# JetsonTK1_GPIO.net
KiCad netlist of a schematic drawn in EAGLE
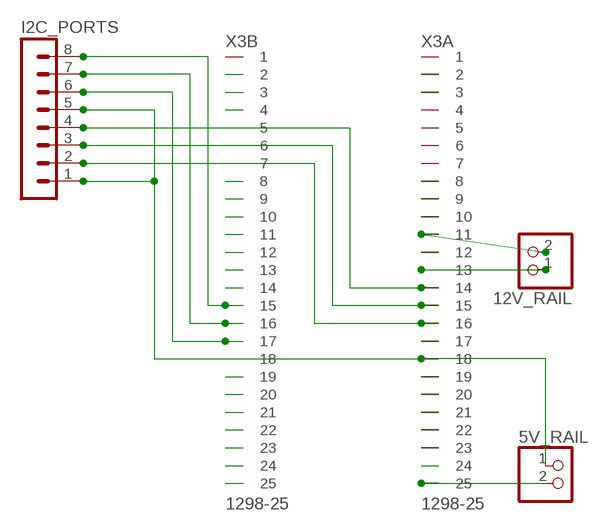
[diagram p0: schematic, sheet 1]

(export (version "E")
  (design (tool "Eeschema 10.0.6"))
  (components
    (comp (ref "5V_RAIL")
      (value "PINHD-1X2")
      (footprint "eagle-import:1X02")
      (libsource (lib "eagle-import") (part "PINHD-1X2"))
    )
    (comp (ref "12V_RAIL")
      (value "PINHD-1X2")
      (footprint "eagle-import:1X02")
      (libsource (lib "eagle-import") (part "PINHD-1X2"))
    )
    (comp (ref "I2C_PORTS")
      (value "MA08-1")
      (footprint "eagle-import:MA08-1")
      (libsource (lib "eagle-import") (part "MA08-1"))
    )
    (comp (ref "X3")
      (value "1298-25")
      (footprint "eagle-import:1298-25")
      (libsource (lib "eagle-import") (part "1298-25"))
    )
  )
  (nets
    (net (code "1") (name "Net-(X3A-11)") (class "Default")
      (node (ref "12V_RAIL") (pin "2") (pinfunction "2_2") (pintype "passive"))
      (node (ref "X3") (pin "A11") (pinfunction "11_A11") (pintype "passive"))
    )
    (net (code "2") (name "Net-(X3A-13)") (class "Default")
      (node (ref "12V_RAIL") (pin "1") (pinfunction "1_1") (pintype "passive"))
      (node (ref "X3") (pin "A13") (pinfunction "13_A13") (pintype "passive"))
    )
    (net (code "3") (name "Net-(X3A-14)") (class "Default")
      (node (ref "I2C_PORTS") (pin "4") (pinfunction "4_4") (pintype "passive"))
      (node (ref "X3") (pin "A14") (pinfunction "14_A14") (pintype "passive"))
    )
    (net (code "4") (name "Net-(X3A-15)") (class "Default")
      (node (ref "I2C_PORTS") (pin "3") (pinfunction "3_3") (pintype "passive"))
      (node (ref "X3") (pin "A15") (pinfunction "15_A15") (pintype "passive"))
    )
    (net (code "5") (name "Net-(X3A-16)") (class "Default")
      (node (ref "I2C_PORTS") (pin "2") (pinfunction "2_2") (pintype "passive"))
      (node (ref "X3") (pin "A16") (pinfunction "16_A16") (pintype "passive"))
    )
    (net (code "6") (name "Net-(X3A-18)") (class "Default")
      (node (ref "5V_RAIL") (pin "1") (pinfunction "1_1") (pintype "passive"))
      (node (ref "I2C_PORTS") (pin "1") (pinfunction "1_1") (pintype "passive"))
      (node (ref "I2C_PORTS") (pin "5") (pinfunction "5_5") (pintype "passive"))
      (node (ref "X3") (pin "A18") (pinfunction "18_A18") (pintype "passive"))
    )
    (net (code "7") (name "Net-(X3A-25)") (class "Default")
      (node (ref "5V_RAIL") (pin "2") (pinfunction "2_2") (pintype "passive"))
      (node (ref "X3") (pin "A25") (pinfunction "25_A25") (pintype "passive"))
    )
    (net (code "8") (name "Net-(X3B-15)") (class "Default")
      (node (ref "I2C_PORTS") (pin "8") (pinfunction "8_8") (pintype "passive"))
      (node (ref "X3") (pin "B15") (pinfunction "15_B15") (pintype "passive"))
    )
    (net (code "9") (name "Net-(X3B-16)") (class "Default")
      (node (ref "I2C_PORTS") (pin "7") (pinfunction "7_7") (pintype "passive"))
      (node (ref "X3") (pin "B16") (pinfunction "16_B16") (pintype "passive"))
    )
    (net (code "10") (name "Net-(X3B-17)") (class "Default")
      (node (ref "I2C_PORTS") (pin "6") (pinfunction "6_6") (pintype "passive"))
      (node (ref "X3") (pin "B17") (pinfunction "17_B17") (pintype "passive"))
    )
    (net (code "11") (name "unconnected-(X3A-1-PadA1)") (class "Default")
      (node (ref "X3") (pin "A1") (pinfunction "1_A1") (pintype "passive"))
    )
    (net (code "12") (name "unconnected-(X3A-2-PadA2)") (class "Default")
      (node (ref "X3") (pin "A2") (pinfunction "2_A2") (pintype "passive"))
    )
    (net (code "13") (name "unconnected-(X3A-3-PadA3)") (class "Default")
      (node (ref "X3") (pin "A3") (pinfunction "3_A3") (pintype "passive"))
    )
    (net (code "14") (name "unconnected-(X3A-4-PadA4)") (class "Default")
      (node (ref "X3") (pin "A4") (pinfunction "4_A4") (pintype "passive"))
    )
    (net (code "15") (name "unconnected-(X3A-5-PadA5)") (class "Default")
      (node (ref "X3") (pin "A5") (pinfunction "5_A5") (pintype "passive"))
    )
    (net (code "16") (name "unconnected-(X3A-6-PadA6)") (class "Default")
      (node (ref "X3") (pin "A6") (pinfunction "6_A6") (pintype "passive"))
    )
    (net (code "17") (name "unconnected-(X3A-7-PadA7)") (class "Default")
      (node (ref "X3") (pin "A7") (pinfunction "7_A7") (pintype "passive"))
    )
    (net (code "18") (name "unconnected-(X3A-8-PadA8)") (class "Default")
      (node (ref "X3") (pin "A8") (pinfunction "8_A8") (pintype "passive"))
    )
    (net (code "19") (name "unconnected-(X3A-9-PadA9)") (class "Default")
      (node (ref "X3") (pin "A9") (pinfunction "9_A9") (pintype "passive"))
    )
    (net (code "20") (name "unconnected-(X3A-10-PadA10)") (class "Default")
      (node (ref "X3") (pin "A10") (pinfunction "10_A10") (pintype "passive"))
    )
    (net (code "21") (name "unconnected-(X3A-12-PadA12)") (class "Default")
      (node (ref "X3") (pin "A12") (pinfunction "12_A12") (pintype "passive"))
    )
    (net (code "22") (name "unconnected-(X3A-17-PadA17)") (class "Default")
      (node (ref "X3") (pin "A17") (pinfunction "17_A17") (pintype "passive"))
    )
    (net (code "23") (name "unconnected-(X3A-19-PadA19)") (class "Default")
      (node (ref "X3") (pin "A19") (pinfunction "19_A19") (pintype "passive"))
    )
    (net (code "24") (name "unconnected-(X3A-20-PadA20)") (class "Default")
      (node (ref "X3") (pin "A20") (pinfunction "20_A20") (pintype "passive"))
    )
    (net (code "25") (name "unconnected-(X3A-21-PadA21)") (class "Default")
      (node (ref "X3") (pin "A21") (pinfunction "21_A21") (pintype "passive"))
    )
    (net (code "26") (name "unconnected-(X3A-22-PadA22)") (class "Default")
      (node (ref "X3") (pin "A22") (pinfunction "22_A22") (pintype "passive"))
    )
    (net (code "27") (name "unconnected-(X3A-23-PadA23)") (class "Default")
      (node (ref "X3") (pin "A23") (pinfunction "23_A23") (pintype "passive"))
    )
    (net (code "28") (name "unconnected-(X3A-24-PadA24)") (class "Default")
      (node (ref "X3") (pin "A24") (pinfunction "24_A24") (pintype "passive"))
    )
    (net (code "29") (name "unconnected-(X3B-1-PadB1)") (class "Default")
      (node (ref "X3") (pin "B1") (pinfunction "1_B1") (pintype "passive"))
    )
    (net (code "30") (name "unconnected-(X3B-2-PadB2)") (class "Default")
      (node (ref "X3") (pin "B2") (pinfunction "2_B2") (pintype "passive"))
    )
    (net (code "31") (name "unconnected-(X3B-3-PadB3)") (class "Default")
      (node (ref "X3") (pin "B3") (pinfunction "3_B3") (pintype "passive"))
    )
    (net (code "32") (name "unconnected-(X3B-4-PadB4)") (class "Default")
      (node (ref "X3") (pin "B4") (pinfunction "4_B4") (pintype "passive"))
    )
    (net (code "33") (name "unconnected-(X3B-5-PadB5)") (class "Default")
      (node (ref "X3") (pin "B5") (pinfunction "5_B5") (pintype "passive"))
    )
    (net (code "34") (name "unconnected-(X3B-6-PadB6)") (class "Default")
      (node (ref "X3") (pin "B6") (pinfunction "6_B6") (pintype "passive"))
    )
    (net (code "35") (name "unconnected-(X3B-7-PadB7)") (class "Default")
      (node (ref "X3") (pin "B7") (pinfunction "7_B7") (pintype "passive"))
    )
    (net (code "36") (name "unconnected-(X3B-8-PadB8)") (class "Default")
      (node (ref "X3") (pin "B8") (pinfunction "8_B8") (pintype "passive"))
    )
    (net (code "37") (name "unconnected-(X3B-9-PadB9)") (class "Default")
      (node (ref "X3") (pin "B9") (pinfunction "9_B9") (pintype "passive"))
    )
    (net (code "38") (name "unconnected-(X3B-10-PadB10)") (class "Default")
      (node (ref "X3") (pin "B10") (pinfunction "10_B10") (pintype "passive"))
    )
    (net (code "39") (name "unconnected-(X3B-11-PadB11)") (class "Default")
      (node (ref "X3") (pin "B11") (pinfunction "11_B11") (pintype "passive"))
    )
    (net (code "40") (name "unconnected-(X3B-12-PadB12)") (class "Default")
      (node (ref "X3") (pin "B12") (pinfunction "12_B12") (pintype "passive"))
    )
    (net (code "41") (name "unconnected-(X3B-13-PadB13)") (class "Default")
      (node (ref "X3") (pin "B13") (pinfunction "13_B13") (pintype "passive"))
    )
    (net (code "42") (name "unconnected-(X3B-14-PadB14)") (class "Default")
      (node (ref "X3") (pin "B14") (pinfunction "14_B14") (pintype "passive"))
    )
    (net (code "43") (name "unconnected-(X3B-18-PadB18)") (class "Default")
      (node (ref "X3") (pin "B18") (pinfunction "18_B18") (pintype "passive"))
    )
    (net (code "44") (name "unconnected-(X3B-19-PadB19)") (class "Default")
      (node (ref "X3") (pin "B19") (pinfunction "19_B19") (pintype "passive"))
    )
    (net (code "45") (name "unconnected-(X3B-20-PadB20)") (class "Default")
      (node (ref "X3") (pin "B20") (pinfunction "20_B20") (pintype "passive"))
    )
    (net (code "46") (name "unconnected-(X3B-21-PadB21)") (class "Default")
      (node (ref "X3") (pin "B21") (pinfunction "21_B21") (pintype "passive"))
    )
    (net (code "47") (name "unconnected-(X3B-22-PadB22)") (class "Default")
      (node (ref "X3") (pin "B22") (pinfunction "22_B22") (pintype "passive"))
    )
    (net (code "48") (name "unconnected-(X3B-23-PadB23)") (class "Default")
      (node (ref "X3") (pin "B23") (pinfunction "23_B23") (pintype "passive"))
    )
    (net (code "49") (name "unconnected-(X3B-24-PadB24)") (class "Default")
      (node (ref "X3") (pin "B24") (pinfunction "24_B24") (pintype "passive"))
    )
    (net (code "50") (name "unconnected-(X3B-25-PadB25)") (class "Default")
      (node (ref "X3") (pin "B25") (pinfunction "25_B25") (pintype "passive"))
    )
  )
)
